# tape_power_adapter.net
KiCad netlist of a schematic drawn in EAGLE
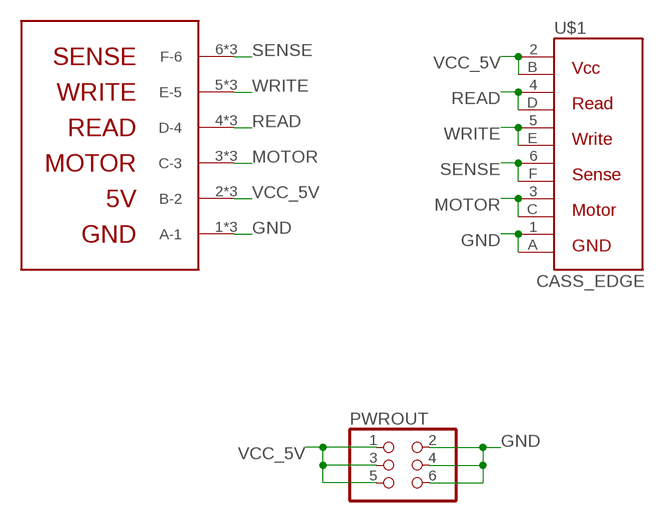
[diagram p0: schematic, sheet 1]

(export (version "E")
  (design (tool "Eeschema 10.0.6"))
  (components
    (comp (ref "PWROUT")
      (value "PINHD-2X03_2.54")
      (footprint "eagle-import:2X03")
      (libsource (lib "eagle-import") (part "PINHD-2X03_2.54"))
    )
    (comp (ref "U$1")
      (value "CASS_EDGE")
      (footprint "eagle-import:12PINEDGE")
      (libsource (lib "eagle-import") (part "CASS_EDGE"))
    )
    (comp (ref "U$2")
      (value "C64CASSCONN")
      (footprint "eagle-import:C64TAPECONN")
      (libsource (lib "eagle-import") (part "C64CASSCONN"))
    )
  )
  (nets
    (net (code "1") (name "GND") (class "Default")
      (node (ref "PWROUT") (pin "2") (pinfunction "2_2") (pintype "passive"))
      (node (ref "PWROUT") (pin "4") (pinfunction "4_4") (pintype "passive"))
      (node (ref "PWROUT") (pin "6") (pinfunction "6_6") (pintype "passive"))
      (node (ref "U$1") (pin "1") (pinfunction "GND1_1") (pintype "passive"))
      (node (ref "U$1") (pin "A") (pinfunction "GND2_A") (pintype "passive"))
      (node (ref "U$2") (pin "1") (pinfunction "A-1_1") (pintype "bidirectional"))
      (node (ref "U$2") (pin "1A") (pinfunction "A-1_1A") (pintype "bidirectional"))
      (node (ref "U$2") (pin "A") (pinfunction "A-1_A") (pintype "bidirectional"))
    )
    (net (code "2") (name "MOTOR") (class "Default")
      (node (ref "U$1") (pin "3") (pinfunction "MOTOR1_3") (pintype "input"))
      (node (ref "U$1") (pin "C") (pinfunction "MOTOR2_C") (pintype "input"))
      (node (ref "U$2") (pin "3") (pinfunction "C-3_3") (pintype "bidirectional"))
      (node (ref "U$2") (pin "3C") (pinfunction "C-3_3C") (pintype "bidirectional"))
      (node (ref "U$2") (pin "C") (pinfunction "C-3_C") (pintype "bidirectional"))
    )
    (net (code "3") (name "READ") (class "Default")
      (node (ref "U$1") (pin "4") (pinfunction "READ1_4") (pintype "output"))
      (node (ref "U$1") (pin "D") (pinfunction "READ2_D") (pintype "passive"))
      (node (ref "U$2") (pin "4") (pinfunction "D-4_4") (pintype "bidirectional"))
      (node (ref "U$2") (pin "4D") (pinfunction "D-4_4D") (pintype "bidirectional"))
      (node (ref "U$2") (pin "D") (pinfunction "D-4_D") (pintype "bidirectional"))
    )
    (net (code "4") (name "SENSE") (class "Default")
      (node (ref "U$1") (pin "6") (pinfunction "SENSE1_6") (pintype "output"))
      (node (ref "U$1") (pin "F") (pinfunction "SENSE2_F") (pintype "passive"))
      (node (ref "U$2") (pin "6") (pinfunction "F-6_6") (pintype "bidirectional"))
      (node (ref "U$2") (pin "6F") (pinfunction "F-6_6F") (pintype "bidirectional"))
      (node (ref "U$2") (pin "F") (pinfunction "F-6_F") (pintype "bidirectional"))
    )
    (net (code "5") (name "VCC_5V") (class "Default")
      (node (ref "PWROUT") (pin "1") (pinfunction "1_1") (pintype "passive"))
      (node (ref "PWROUT") (pin "3") (pinfunction "3_3") (pintype "passive"))
      (node (ref "PWROUT") (pin "5") (pinfunction "5_5") (pintype "passive"))
      (node (ref "U$1") (pin "2") (pinfunction "VCC1_2") (pintype "passive"))
      (node (ref "U$1") (pin "B") (pinfunction "VCC2_B") (pintype "passive"))
      (node (ref "U$2") (pin "2") (pinfunction "B-2_2") (pintype "bidirectional"))
      (node (ref "U$2") (pin "2B") (pinfunction "B-2_2B") (pintype "bidirectional"))
      (node (ref "U$2") (pin "B") (pinfunction "B-2_B") (pintype "bidirectional"))
    )
    (net (code "6") (name "WRITE") (class "Default")
      (node (ref "U$1") (pin "5") (pinfunction "WRITE1_5") (pintype "input"))
      (node (ref "U$1") (pin "E") (pinfunction "WRITE2_E") (pintype "input"))
      (node (ref "U$2") (pin "5") (pinfunction "E-5_5") (pintype "bidirectional"))
      (node (ref "U$2") (pin "5E") (pinfunction "E-5_5E") (pintype "bidirectional"))
      (node (ref "U$2") (pin "E") (pinfunction "E-5_E") (pintype "bidirectional"))
    )
  )
)
